# Infrarouge_R_T_LED_SMD.net
KiCad netlist of a schematic drawn in Altium Designer
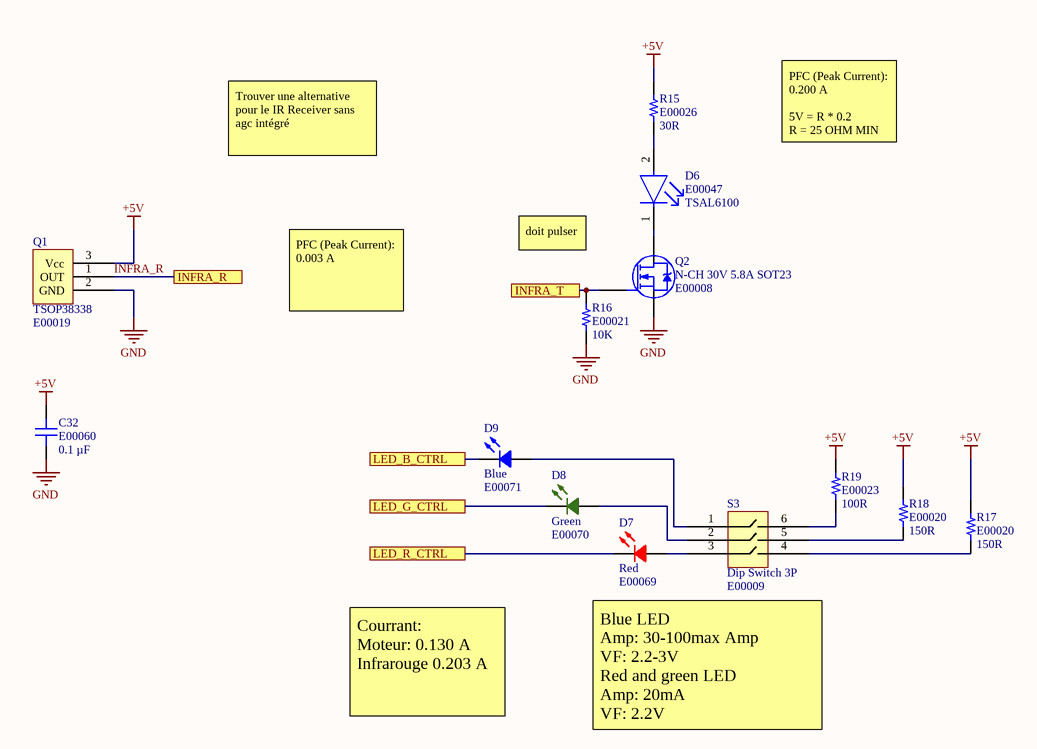
[diagram p0: Infrarouge R&T, LED SMD.SchDoc]

(export (version "E")
  (design (tool "Eeschema 10.0.6"))
  (components
    (comp (ref "C32")
      (value "0.1 µF")
      (footprint "CAP 0603")
      (description "CAP CER 0.1UF 50V X7R 0603")
      (fields
        (field (name "MANUFACTURER") "KEMET")
        (field (name "TOLERANCE") "±10%")
        (field (name "ADAM INVENTORY NUMBER 1") "E00060")
      )
      (libsource (lib "ADAM LIBRARY") (part "CAP CER 0.1UF 50V X7R 0603"))
    )
    (comp (ref "D6")
      (value "TSAL6100")
      (footprint "IR TRANSMITTER")
      (description "Infrared (IR) Emitter 940nm 1.35V 100mA 80mW/sr @ 100mA 20° Radial, 5mm Dia (T 1 3/4)")
      (fields
        (field (name "ADAM INVENTORY NUMBER 1") "E00047")
        (field (name "MANUFACTURER PART NUMBER 1") "TSAL6100")
      )
      (libsource (lib "ADAM LIBRARY") (part "TSAL6100"))
    )
    (comp (ref "D7")
      (value "Red")
      (footprint "Red Led 0603")
      (description "0603 RED LED")
      (fields
        (field (name "MANUFACTURER") "American Bright Optoelectronics Corporation")
        (field (name "ADAM INVENTORY NUMBER 1") "E00069")
      )
      (libsource (lib "ADAM LIBRARY") (part "0603 RED LED"))
    )
    (comp (ref "D8")
      (value "Green")
      (footprint "Green LED 0603")
      (description "LED GREEN 0603 SMD")
      (fields (field (name "MANUFACTURER") "Dialight") (field (name "ADAM INVENTORY NUMBER 1") "E00070"))
      (libsource (lib "ADAM LIBRARY") (part "0603 GREEN LED"))
    )
    (comp (ref "D9")
      (value "Blue")
      (footprint "Blue LED 0603")
      (description "Blue 470nm LED Indication - Discrete 3.3V 0603 (1608 Metric)")
      (fields (field (name "ADAM INVENTORY NUMBER 1") "E00071"))
      (libsource (lib "ADAM LIBRARY") (part "0603 BLUE LED"))
    )
    (comp (ref "Q1")
      (value "TSOP38338")
      (footprint "IR Receptor")
      (description "Remote Receiver Sensor 38.0kHz 45m Through Hole")
      (fields (field (name "ADAM INVENTORY NUMBER 1") "E00019"))
      (libsource (lib "ADAM LIBRARY") (part "TSOP38338 IR Sensor-Symbol-1"))
    )
    (comp (ref "Q2")
      (value "N-CH 30V 5.8A SOT23")
      (footprint "N-CHANNEL TRANS")
      (description "N-Channel 5.8A (Tj) 350mW Surface Mount SOT-23")
      (fields (field (name "MANUFACTURER") "MCC") (field (name "ADAM INVENTORY NUMBER 1") "E00008"))
      (libsource (lib "ADAM LIBRARY") (part "TRANS N-CHANNEL 30V 5.8A SOT23"))
    )
    (comp (ref "R15")
      (value "30R")
      (footprint "RES 0603")
      (description "RES 30 OHM 1% 1/3W 0603")
      (fields
        (field (name "MANUFACTURER") "KOA Speer Electronics, Inc.")
        (field (name "TOLERANCE") "±1%")
        (field (name "ADAM INVENTORY NUMBER 1") "E00026")
      )
      (libsource (lib "ADAM LIBRARY") (part "RES SMD 30 OHM"))
    )
    (comp (ref "R16")
      (value "10K")
      (footprint "RES 0603")
      (description "RES SMD 10K OHM 1% 1/10W 0603")
      (fields
        (field (name "MANUFACTURER") "Rohm Semiconductor")
        (field (name "TOLERANCE") "±1%")
        (field (name "ADAM INVENTORY NUMBER 1") "E00021")
      )
      (libsource (lib "ADAM LIBRARY") (part "RES SMD 10K OHM"))
    )
    (comp (ref "R17")
      (value "150R")
      (footprint "RES 0603")
      (description "RES SMD 150 OHM 0.1% 1/8W 0603")
      (fields
        (field (name "MANUFACTURER") "Vishay Beyschlag")
        (field (name "TOLERANCE") "±0.1%")
        (field (name "ADAM INVENTORY NUMBER 1") "E00020")
      )
      (libsource (lib "ADAM LIBRARY") (part "RES SMD 150 OHM"))
    )
    (comp (ref "R18")
      (value "150R")
      (footprint "RES 0603")
      (description "RES SMD 150 OHM 0.1% 1/8W 0603")
      (fields
        (field (name "MANUFACTURER") "Vishay Beyschlag")
        (field (name "TOLERANCE") "±0.1%")
        (field (name "ADAM INVENTORY NUMBER 1") "E00020")
      )
      (libsource (lib "ADAM LIBRARY") (part "RES SMD 150 OHM"))
    )
    (comp (ref "R19")
      (value "100R")
      (footprint "RES 0603")
      (description "RESISTOR 100 Ohm SMD 1% 1/10W")
      (fields
        (field (name "MANUFACTURER") "Yageo")
        (field (name "TOLERANCE") "±1%")
        (field (name "ADAM INVENTORY NUMBER 1") "E00023")
      )
      (libsource (lib "ADAM LIBRARY") (part "RES SMD 100 OHM"))
    )
    (comp (ref "S3")
      (value "Dip Switch 3P")
      (footprint "DIPSWITCH SMD 3P")
      (description "Dip Switch SPST 3 Position Surface Mount Slide (Standard) Actuator 25mA 24VDC")
      (fields (field (name "MANUFACTURER") "CUI") (field (name "ADAM INVENTORY NUMBER 1") "E00009"))
      (libsource (lib "ADAM LIBRARY") (part "Dip Switch 3P"))
    )
  )
  (nets
    (net (code "1") (name "+5V") (class "Default")
      (node (ref "C32") (pin "2") (pinfunction "2_2") (pintype "passive"))
      (node (ref "Q1") (pin "3") (pinfunction "Vcc_3") (pintype "passive"))
      (node (ref "R15") (pin "2") (pinfunction "2_2") (pintype "passive"))
      (node (ref "R17") (pin "2") (pinfunction "2_2") (pintype "passive"))
      (node (ref "R18") (pin "2") (pinfunction "2_2") (pintype "passive"))
      (node (ref "R19") (pin "2") (pinfunction "2_2") (pintype "passive"))
    )
    (net (code "2") (name "/INFRA_R") (class "Default")
      (node (ref "Q1") (pin "1") (pinfunction "OUT_1") (pintype "passive"))
    )
    (net (code "3") (name "/INFRA_T") (class "Default")
      (node (ref "Q2") (pin "1") (pinfunction "G_1") (pintype "passive"))
      (node (ref "R16") (pin "2") (pinfunction "2_2") (pintype "passive"))
    )
    (net (code "4") (name "/LED_B_CTRL") (class "Default")
      (node (ref "D9") (pin "2") (pinfunction "2_2") (pintype "passive"))
    )
    (net (code "5") (name "/LED_G_CTRL") (class "Default")
      (node (ref "D8") (pin "2") (pinfunction "2_2") (pintype "passive"))
    )
    (net (code "6") (name "/LED_R_CTRL") (class "Default")
      (node (ref "D7") (pin "2") (pinfunction "2_2") (pintype "passive"))
    )
    (net (code "7") (name "GND") (class "Default")
      (node (ref "C32") (pin "1") (pinfunction "1_1") (pintype "passive"))
      (node (ref "Q1") (pin "2") (pinfunction "GND_2") (pintype "passive"))
      (node (ref "Q2") (pin "2") (pinfunction "S_2") (pintype "passive"))
      (node (ref "R16") (pin "1") (pinfunction "1_1") (pintype "passive"))
    )
    (net (code "8") (name "Net-(D6-A)") (class "Default")
      (node (ref "D6") (pin "2") (pinfunction "A_2") (pintype "passive"))
      (node (ref "R15") (pin "1") (pinfunction "1_1") (pintype "passive"))
    )
    (net (code "9") (name "Net-(D6-C)") (class "Default")
      (node (ref "D6") (pin "1") (pinfunction "C_1") (pintype "passive"))
      (node (ref "Q2") (pin "3") (pinfunction "D_3") (pintype "passive"))
    )
    (net (code "10") (name "Net-(D7-Pad1)") (class "Default")
      (node (ref "D7") (pin "1") (pinfunction "1_1") (pintype "passive"))
      (node (ref "S3") (pin "3") (pinfunction "3_3") (pintype "passive"))
    )
    (net (code "11") (name "Net-(D8-Pad1)") (class "Default")
      (node (ref "D8") (pin "1") (pinfunction "1_1") (pintype "passive"))
      (node (ref "S3") (pin "2") (pinfunction "2_2") (pintype "passive"))
    )
    (net (code "12") (name "Net-(D9-Pad1)") (class "Default")
      (node (ref "D9") (pin "1") (pinfunction "1_1") (pintype "passive"))
      (node (ref "S3") (pin "1") (pinfunction "1_1") (pintype "passive"))
    )
    (net (code "13") (name "Net-(R17-Pad1)") (class "Default")
      (node (ref "R17") (pin "1") (pinfunction "1_1") (pintype "passive"))
      (node (ref "S3") (pin "4") (pinfunction "4_4") (pintype "passive"))
    )
    (net (code "14") (name "Net-(R18-Pad1)") (class "Default")
      (node (ref "R18") (pin "1") (pinfunction "1_1") (pintype "passive"))
      (node (ref "S3") (pin "5") (pinfunction "5_5") (pintype "passive"))
    )
    (net (code "15") (name "Net-(R19-Pad1)") (class "Default")
      (node (ref "R19") (pin "1") (pinfunction "1_1") (pintype "passive"))
      (node (ref "S3") (pin "6") (pinfunction "6_6") (pintype "passive"))
    )
  )
)
